# Audio_Output_Line_Out.net
KiCad netlist of a schematic drawn in Altium Designer
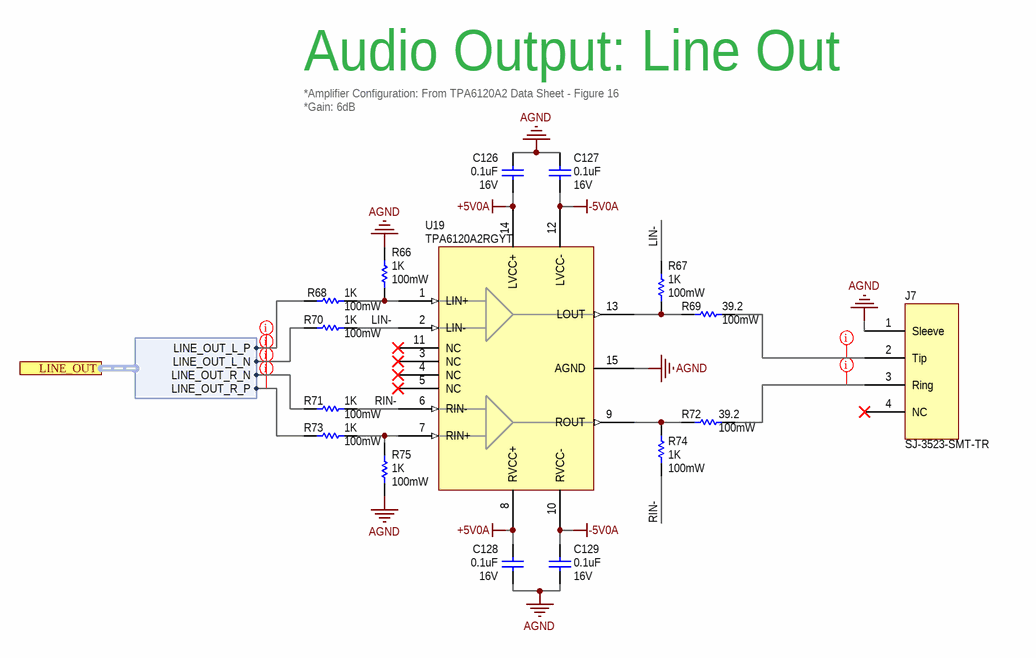
[diagram p0: Audio_Output_Line_Out.SchDoc]

(export (version "E")
  (design (tool "Eeschema 10.0.6"))
  (components
    (comp (ref "C126")
      (value "CL10F104ZO8NNNC")
      (footprint "3-0603_L")
      (description "CAP CER 0.1UF 16V Y5V 0603")
      (fields
        (field (name "MANUFACTURER") "Samsung")
        (field (name "TOLERANCE") "80%")
        (field (name "VOLTAGE RATING") "16V")
        (field (name "CAPACITANCE") "0.1uF")
      )
      (libsource (lib "Schematic_Components_CD") (part "CL10F104ZO8NNNC"))
    )
    (comp (ref "C127")
      (value "CL10F104ZO8NNNC")
      (footprint "3-0603_L")
      (description "CAP CER 0.1UF 16V Y5V 0603")
      (fields
        (field (name "MANUFACTURER") "Samsung")
        (field (name "TOLERANCE") "80%")
        (field (name "VOLTAGE RATING") "16V")
        (field (name "CAPACITANCE") "0.1uF")
      )
      (libsource (lib "Schematic_Components_CD") (part "CL10F104ZO8NNNC"))
    )
    (comp (ref "C128")
      (value "CL10F104ZO8NNNC")
      (footprint "3-0603_L")
      (description "CAP CER 0.1UF 16V Y5V 0603")
      (fields
        (field (name "MANUFACTURER") "Samsung")
        (field (name "TOLERANCE") "80%")
        (field (name "VOLTAGE RATING") "16V")
        (field (name "CAPACITANCE") "0.1uF")
      )
      (libsource (lib "Schematic_Components_CD") (part "CL10F104ZO8NNNC"))
    )
    (comp (ref "C129")
      (value "CL10F104ZO8NNNC")
      (footprint "3-0603_L")
      (description "CAP CER 0.1UF 16V Y5V 0603")
      (fields
        (field (name "MANUFACTURER") "Samsung")
        (field (name "TOLERANCE") "80%")
        (field (name "VOLTAGE RATING") "16V")
        (field (name "CAPACITANCE") "0.1uF")
      )
      (libsource (lib "Schematic_Components_CD") (part "CL10F104ZO8NNNC"))
    )
    (comp (ref "J7")
      (value "SJ-3523-SMT-TR")
      (footprint "SJ-3523-SMT-TR")
      (description "3.50mm (0.141\", 1/8\", Mini Plug) - Headphone Phone Jack Stereo Connector Solder")
      (fields
        (field (name "MANUFACTURER") "CUI Inc.")
        (field (name "MANUFACTURER PART NUMBER") "SJ-3523-SMT-TR")
        (field (name "PUBLISHER") "Altium Limited")
      )
      (libsource (lib "NIH_DE0_Nano_Daughter_Card_Library") (part "SJ-3523-SMT-TR"))
    )
    (comp (ref "R66")
      (value "ERJ-3EKF1001V")
      (footprint "3-0603_R_L")
      (description "RES 1.00K OHM 1/10W 1% 0603 SMD")
      (fields
        (field (name "MANUFACTURER") "Panasonic - ECG")
        (field (name "POWER (WATTS)") "100mW")
        (field (name "TOLERANCE") "±1%")
        (field (name "RESISTANCE (OHMS)") "1K")
      )
      (libsource (lib "Schematic_Components") (part "ERJ-3EKF1001V"))
    )
    (comp (ref "R67")
      (value "ERJ-3EKF1001V")
      (footprint "3-0603_R_L")
      (description "RES 1.00K OHM 1/10W 1% 0603 SMD")
      (fields
        (field (name "MANUFACTURER") "Panasonic - ECG")
        (field (name "POWER (WATTS)") "100mW")
        (field (name "TOLERANCE") "±1%")
        (field (name "RESISTANCE (OHMS)") "1K")
      )
      (libsource (lib "Schematic_Components") (part "ERJ-3EKF1001V"))
    )
    (comp (ref "R68")
      (value "ERJ-3EKF1001V")
      (footprint "3-0603_R_L")
      (description "RES 1.00K OHM 1/10W 1% 0603 SMD")
      (fields
        (field (name "MANUFACTURER") "Panasonic - ECG")
        (field (name "POWER (WATTS)") "100mW")
        (field (name "TOLERANCE") "±1%")
        (field (name "RESISTANCE (OHMS)") "1K")
      )
      (libsource (lib "Schematic_Components") (part "ERJ-3EKF1001V"))
    )
    (comp (ref "R69")
      (value "ERJ-3EKF39R2V")
      (footprint "3-0603_R_L")
      (description "n RES SMD 39.2 OHM 1% 1/10W 0603")
      (fields
        (field (name "MANUFACTURER") "Panasonic Electronic Components")
        (field (name "TOLERANCE") "±1%")
        (field (name "POWER (WATTS)") "100mW")
        (field (name "RESISTANCE (OHMS)") "39.2")
      )
      (libsource (lib "Schematic_Components") (part "ERJ-3EKF39R2V"))
    )
    (comp (ref "R70")
      (value "ERJ-3EKF1001V")
      (footprint "3-0603_R_L")
      (description "RES 1.00K OHM 1/10W 1% 0603 SMD")
      (fields
        (field (name "MANUFACTURER") "Panasonic - ECG")
        (field (name "POWER (WATTS)") "100mW")
        (field (name "TOLERANCE") "±1%")
        (field (name "RESISTANCE (OHMS)") "1K")
      )
      (libsource (lib "Schematic_Components") (part "ERJ-3EKF1001V"))
    )
    (comp (ref "R71")
      (value "ERJ-3EKF1001V")
      (footprint "3-0603_R_L")
      (description "RES 1.00K OHM 1/10W 1% 0603 SMD")
      (fields
        (field (name "MANUFACTURER") "Panasonic - ECG")
        (field (name "POWER (WATTS)") "100mW")
        (field (name "TOLERANCE") "±1%")
        (field (name "RESISTANCE (OHMS)") "1K")
      )
      (libsource (lib "Schematic_Components") (part "ERJ-3EKF1001V"))
    )
    (comp (ref "R72")
      (value "ERJ-3EKF39R2V")
      (footprint "3-0603_R_L")
      (description "n RES SMD 39.2 OHM 1% 1/10W 0603")
      (fields
        (field (name "MANUFACTURER") "Panasonic Electronic Components")
        (field (name "TOLERANCE") "±1%")
        (field (name "POWER (WATTS)") "100mW")
        (field (name "RESISTANCE (OHMS)") "39.2")
      )
      (libsource (lib "Schematic_Components") (part "ERJ-3EKF39R2V"))
    )
    (comp (ref "R73")
      (value "ERJ-3EKF1001V")
      (footprint "3-0603_R_L")
      (description "RES 1.00K OHM 1/10W 1% 0603 SMD")
      (fields
        (field (name "MANUFACTURER") "Panasonic - ECG")
        (field (name "POWER (WATTS)") "100mW")
        (field (name "TOLERANCE") "±1%")
        (field (name "RESISTANCE (OHMS)") "1K")
      )
      (libsource (lib "Schematic_Components") (part "ERJ-3EKF1001V"))
    )
    (comp (ref "R74")
      (value "ERJ-3EKF1001V")
      (footprint "3-0603_R_L")
      (description "RES 1.00K OHM 1/10W 1% 0603 SMD")
      (fields
        (field (name "MANUFACTURER") "Panasonic - ECG")
        (field (name "POWER (WATTS)") "100mW")
        (field (name "TOLERANCE") "±1%")
        (field (name "RESISTANCE (OHMS)") "1K")
      )
      (libsource (lib "Schematic_Components") (part "ERJ-3EKF1001V"))
    )
    (comp (ref "R75")
      (value "ERJ-3EKF1001V")
      (footprint "3-0603_R_L")
      (description "RES 1.00K OHM 1/10W 1% 0603 SMD")
      (fields
        (field (name "MANUFACTURER") "Panasonic - ECG")
        (field (name "POWER (WATTS)") "100mW")
        (field (name "TOLERANCE") "±1%")
        (field (name "RESISTANCE (OHMS)") "1K")
      )
      (libsource (lib "Schematic_Components") (part "ERJ-3EKF1001V"))
    )
    (comp (ref "U19")
      (value "TPA6120A2RGYT")
      (footprint "PQFN50P350X350X100_HS-15N")
      (description "Amplifier IC Headphones, 2-Channel (Stereo) Class AB 14-VQFN (3.5x3.5)")
      (fields
        (field (name "MANUFACTURER") "Texas Instruments")
        (field (name "MANUFACTURER PART NUMBER") "TPA6120A2RGYT")
        (field (name "PUBLISHER") "Altium Limited")
      )
      (libsource (lib "Schematic_Components_CD") (part "TPA6120A2RGYT"))
    )
  )
  (nets
    (net (code "2") (name "+5V0A") (class "Default")
      (node (ref "C126") (pin "2") (pinfunction "2_2") (pintype "passive"))
      (node (ref "C128") (pin "1") (pinfunction "1_1") (pintype "passive"))
      (node (ref "U19") (pin "14") (pinfunction "LVCC+_14") (pintype "passive"))
      (node (ref "U19") (pin "8") (pinfunction "RVCC+_8") (pintype "passive"))
    )
    (net (code "3") (name "-5V0A") (class "Default")
      (node (ref "C127") (pin "2") (pinfunction "2_2") (pintype "passive"))
      (node (ref "C129") (pin "1") (pinfunction "1_1") (pintype "passive"))
      (node (ref "U19") (pin "10") (pinfunction "RVCC-_10") (pintype "passive"))
      (node (ref "U19") (pin "12") (pinfunction "LVCC-_12") (pintype "passive"))
    )
    (net (code "4") (name "/LIN-") (class "Default")
      (node (ref "R67") (pin "1") (pinfunction "1_1") (pintype "passive"))
      (node (ref "R70") (pin "2") (pinfunction "2_2") (pintype "passive"))
      (node (ref "U19") (pin "2") (pinfunction "LIN-_2") (pintype "input"))
    )
    (net (code "5") (name "/LINE_OUT_L_N") (class "Default")
      (node (ref "R70") (pin "1") (pinfunction "1_1") (pintype "passive"))
    )
    (net (code "6") (name "/LINE_OUT_L_P") (class "Default")
      (node (ref "R68") (pin "1") (pinfunction "1_1") (pintype "passive"))
    )
    (net (code "7") (name "/LINE_OUT_R_N") (class "Default")
      (node (ref "R71") (pin "1") (pinfunction "1_1") (pintype "passive"))
    )
    (net (code "8") (name "/LINE_OUT_R_P") (class "Default")
      (node (ref "R73") (pin "1") (pinfunction "1_1") (pintype "passive"))
    )
    (net (code "9") (name "/RIN-") (class "Default")
      (node (ref "R71") (pin "2") (pinfunction "2_2") (pintype "passive"))
      (node (ref "R74") (pin "2") (pinfunction "2_2") (pintype "passive"))
      (node (ref "U19") (pin "6") (pinfunction "RIN-_6") (pintype "input"))
    )
    (net (code "11") (name "AGND") (class "Default")
      (node (ref "C126") (pin "1") (pinfunction "1_1") (pintype "passive"))
      (node (ref "C127") (pin "1") (pinfunction "1_1") (pintype "passive"))
      (node (ref "C128") (pin "2") (pinfunction "2_2") (pintype "passive"))
      (node (ref "C129") (pin "2") (pinfunction "2_2") (pintype "passive"))
      (node (ref "J7") (pin "1") (pinfunction "Sleeve_1") (pintype "passive"))
      (node (ref "R66") (pin "2") (pinfunction "2_2") (pintype "passive"))
      (node (ref "R75") (pin "1") (pinfunction "1_1") (pintype "passive"))
      (node (ref "U19") (pin "15") (pinfunction "AGND_15") (pintype "passive"))
    )
    (net (code "12") (name "Net-(J7-Ring)") (class "Default")
      (node (ref "J7") (pin "3") (pinfunction "Ring_3") (pintype "passive"))
      (node (ref "R72") (pin "2") (pinfunction "2_2") (pintype "passive"))
    )
    (net (code "13") (name "Net-(J7-Tip)") (class "Default")
      (node (ref "J7") (pin "2") (pinfunction "Tip_2") (pintype "passive"))
      (node (ref "R69") (pin "2") (pinfunction "2_2") (pintype "passive"))
    )
    (net (code "14") (name "Net-(U19-LIN+)") (class "Default")
      (node (ref "R66") (pin "1") (pinfunction "1_1") (pintype "passive"))
      (node (ref "R68") (pin "2") (pinfunction "2_2") (pintype "passive"))
      (node (ref "U19") (pin "1") (pinfunction "LIN+_1") (pintype "input"))
    )
    (net (code "15") (name "Net-(U19-LOUT)") (class "Default")
      (node (ref "R67") (pin "2") (pinfunction "2_2") (pintype "passive"))
      (node (ref "R69") (pin "1") (pinfunction "1_1") (pintype "passive"))
      (node (ref "U19") (pin "13") (pinfunction "LOUT_13") (pintype "output"))
    )
    (net (code "16") (name "Net-(U19-RIN+)") (class "Default")
      (node (ref "R73") (pin "2") (pinfunction "2_2") (pintype "passive"))
      (node (ref "R75") (pin "2") (pinfunction "2_2") (pintype "passive"))
      (node (ref "U19") (pin "7") (pinfunction "RIN+_7") (pintype "input"))
    )
    (net (code "17") (name "Net-(U19-ROUT)") (class "Default")
      (node (ref "R72") (pin "1") (pinfunction "1_1") (pintype "passive"))
      (node (ref "R74") (pin "1") (pinfunction "1_1") (pintype "passive"))
      (node (ref "U19") (pin "9") (pinfunction "ROUT_9") (pintype "output"))
    )
    (net (code "18") (name "unconnected-(J7-NC-Pad4)") (class "Default")
      (node (ref "J7") (pin "4") (pinfunction "NC_4") (pintype "passive+no_connect"))
    )
    (net (code "19") (name "unconnected-(U19-NC-Pad3)") (class "Default")
      (node (ref "U19") (pin "3") (pinfunction "NC_3") (pintype "passive+no_connect"))
    )
    (net (code "20") (name "unconnected-(U19-NC-Pad4)") (class "Default")
      (node (ref "U19") (pin "4") (pinfunction "NC_4") (pintype "passive+no_connect"))
    )
    (net (code "21") (name "unconnected-(U19-NC-Pad5)") (class "Default")
      (node (ref "U19") (pin "5") (pinfunction "NC_5") (pintype "passive+no_connect"))
    )
    (net (code "22") (name "unconnected-(U19-NC-Pad11)") (class "Default")
      (node (ref "U19") (pin "11") (pinfunction "NC_11") (pintype "passive+no_connect"))
    )
  )
)
